# lamp_board_simple.net
KiCad netlist of a schematic drawn in EAGLE
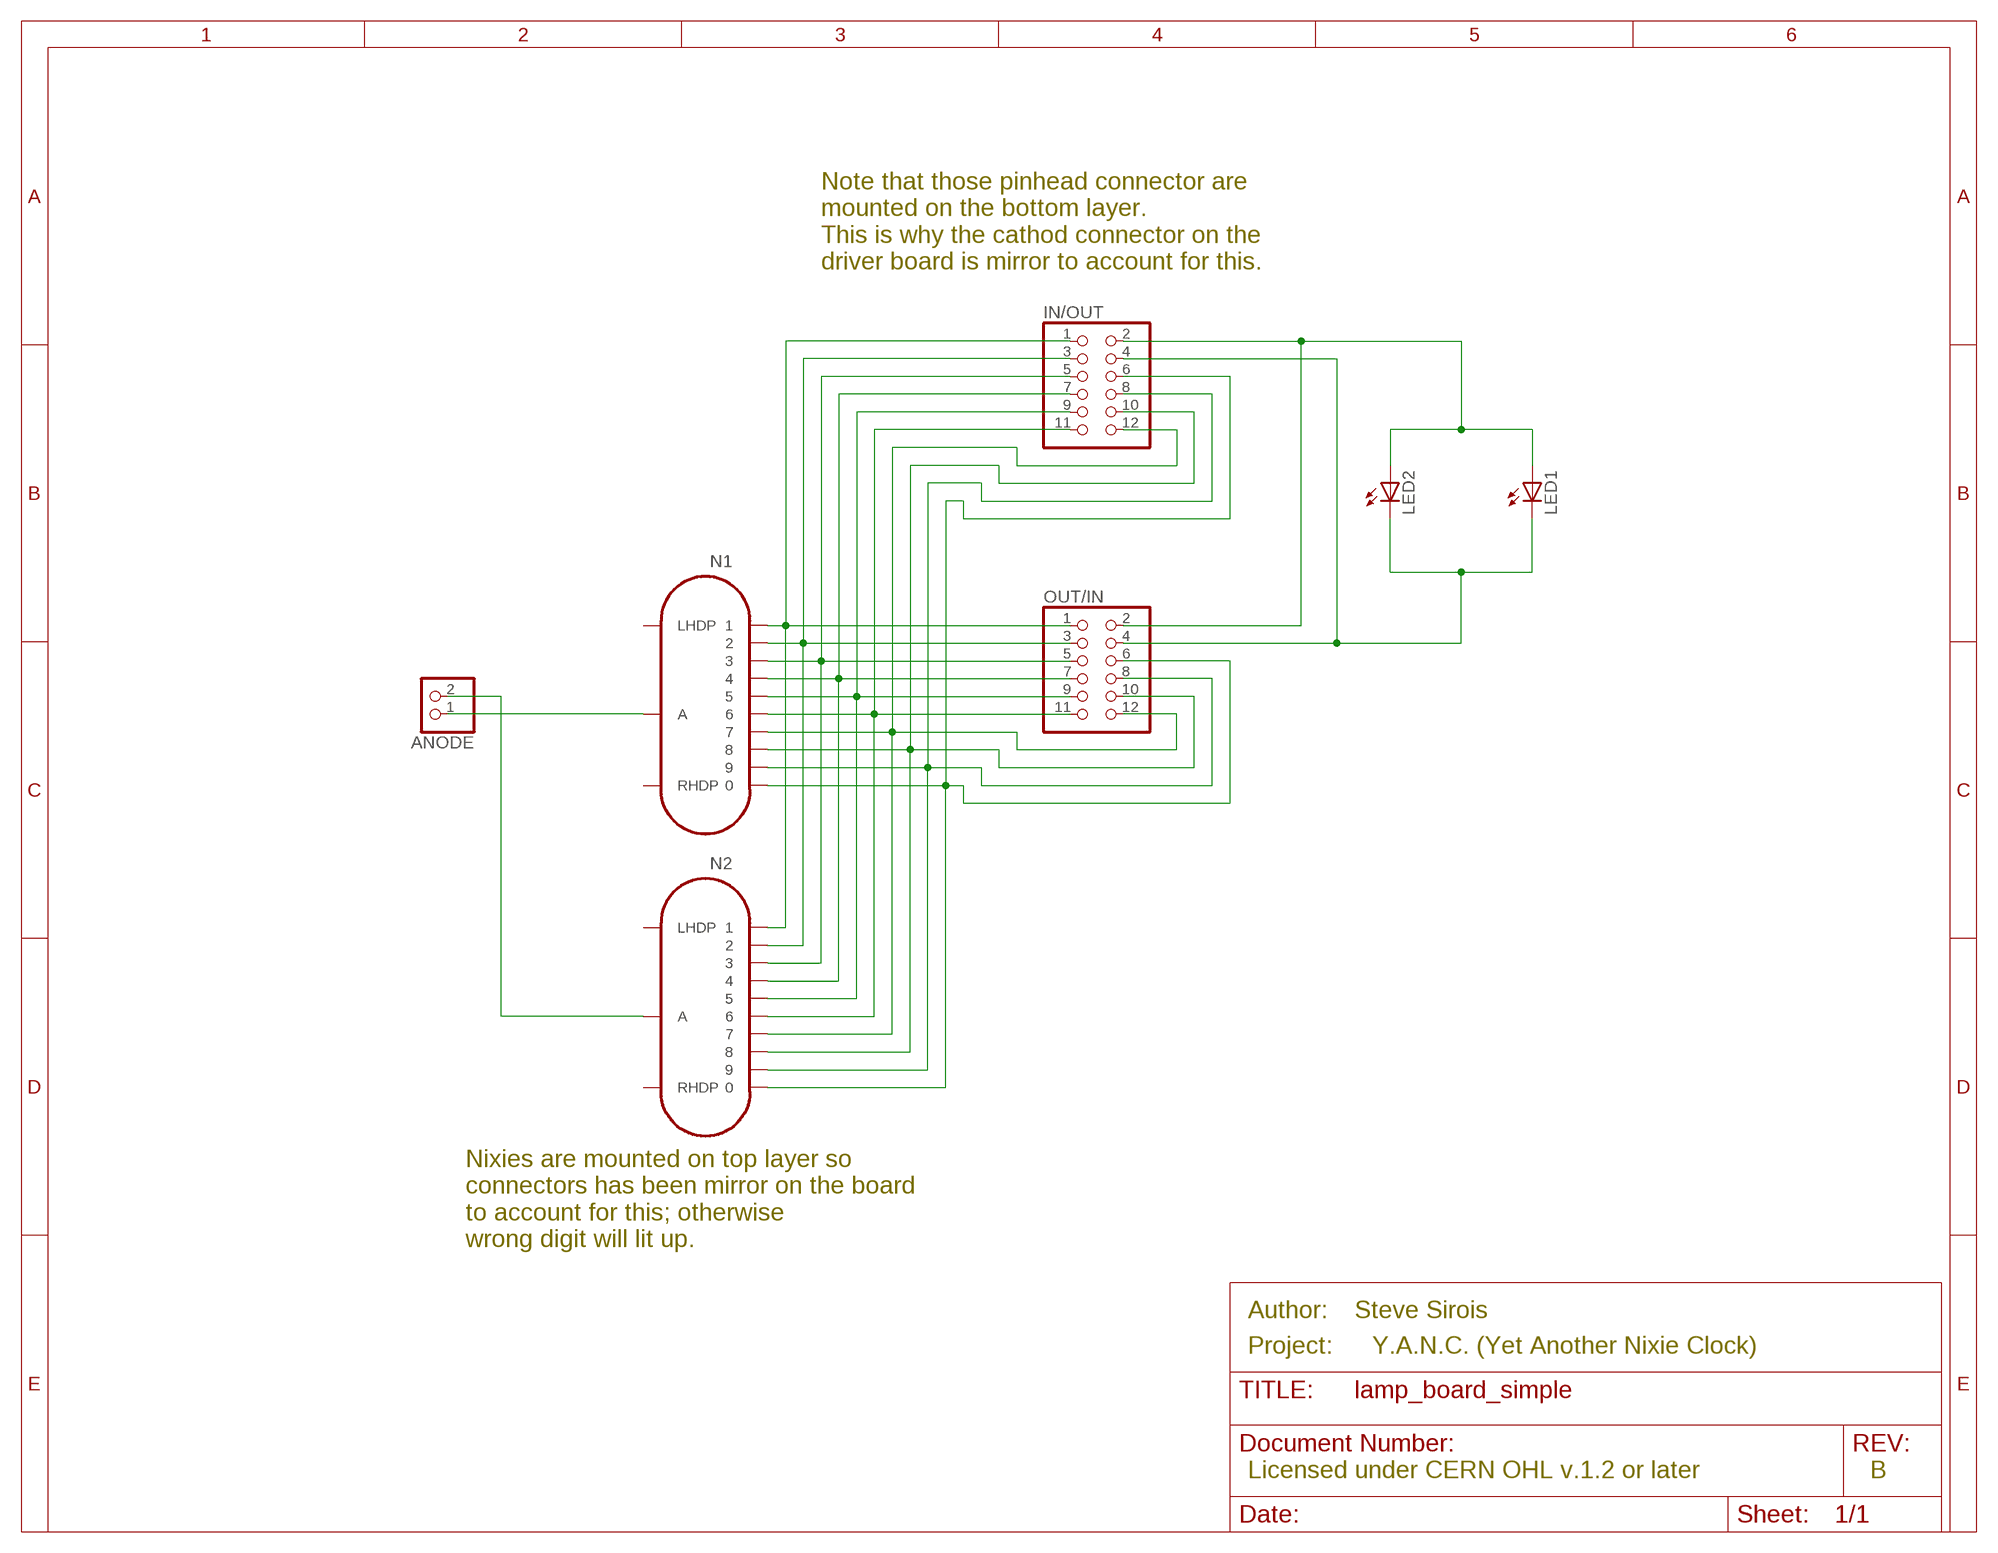
[diagram p0: schematic, sheet 1]

(export (version "E")
  (design (tool "Eeschema 10.0.6"))
  (components
    (comp (ref "ANODE")
      (value "PINHD-1X2/90")
      (footprint "eagle-import:1X02_90")
      (libsource (lib "eagle-import") (part "PINHD-1X2/90"))
    )
    (comp (ref "IN/OUT")
      (value "PINHD-2X6/90")
      (footprint "eagle-import:2X06_90")
      (libsource (lib "eagle-import") (part "PINHD-2X6/90"))
    )
    (comp (ref "LED1")
      (value "LED5MM")
      (footprint "eagle-import:LED5MM")
      (libsource (lib "eagle-import") (part "LED5MM"))
    )
    (comp (ref "LED2")
      (value "LED5MM")
      (footprint "eagle-import:LED5MM")
      (libsource (lib "eagle-import") (part "LED5MM"))
    )
    (comp (ref "N1")
      (value "IN-14")
      (footprint "eagle-import:IN-14")
      (libsource (lib "eagle-import") (part "IN-14"))
    )
    (comp (ref "N2")
      (value "IN-14")
      (footprint "eagle-import:IN-14")
      (libsource (lib "eagle-import") (part "IN-14"))
    )
    (comp (ref "OUT/IN")
      (value "PINHD-2X6/90")
      (footprint "eagle-import:2X06_90")
      (libsource (lib "eagle-import") (part "PINHD-2X6/90"))
    )
  )
  (nets
    (net (code "1") (name "Net-(ANODE-Pad1)") (class "Default")
      (node (ref "ANODE") (pin "1") (pinfunction "1_1") (pintype "passive"))
      (node (ref "N1") (pin "A") (pinfunction "A_A") (pintype "bidirectional"))
    )
    (net (code "2") (name "Net-(ANODE-Pad2)") (class "Default")
      (node (ref "ANODE") (pin "2") (pinfunction "2_2") (pintype "passive"))
      (node (ref "N2") (pin "A") (pinfunction "A_A") (pintype "bidirectional"))
    )
    (net (code "3") (name "Net-(IN/OUT-Pad1)") (class "Default")
      (node (ref "IN/OUT") (pin "1") (pinfunction "1_1") (pintype "passive"))
      (node (ref "N1") (pin "1") (pinfunction "1_1") (pintype "bidirectional"))
      (node (ref "N2") (pin "1") (pinfunction "1_1") (pintype "bidirectional"))
      (node (ref "OUT/IN") (pin "1") (pinfunction "1_1") (pintype "passive"))
    )
    (net (code "4") (name "Net-(IN/OUT-Pad2)") (class "Default")
      (node (ref "IN/OUT") (pin "2") (pinfunction "2_2") (pintype "passive"))
      (node (ref "LED1") (pin "A") (pinfunction "A_A") (pintype "passive"))
      (node (ref "LED2") (pin "A") (pinfunction "A_A") (pintype "passive"))
      (node (ref "OUT/IN") (pin "2") (pinfunction "2_2") (pintype "passive"))
    )
    (net (code "5") (name "Net-(IN/OUT-Pad3)") (class "Default")
      (node (ref "IN/OUT") (pin "3") (pinfunction "3_3") (pintype "passive"))
      (node (ref "N1") (pin "2") (pinfunction "2_2") (pintype "bidirectional"))
      (node (ref "N2") (pin "2") (pinfunction "2_2") (pintype "bidirectional"))
      (node (ref "OUT/IN") (pin "3") (pinfunction "3_3") (pintype "passive"))
    )
    (net (code "6") (name "Net-(IN/OUT-Pad5)") (class "Default")
      (node (ref "IN/OUT") (pin "5") (pinfunction "5_5") (pintype "passive"))
      (node (ref "N1") (pin "3") (pinfunction "3_3") (pintype "bidirectional"))
      (node (ref "N2") (pin "3") (pinfunction "3_3") (pintype "bidirectional"))
      (node (ref "OUT/IN") (pin "5") (pinfunction "5_5") (pintype "passive"))
    )
    (net (code "7") (name "Net-(IN/OUT-Pad6)") (class "Default")
      (node (ref "IN/OUT") (pin "6") (pinfunction "6_6") (pintype "passive"))
      (node (ref "N1") (pin "0") (pinfunction "0_0") (pintype "bidirectional"))
      (node (ref "N2") (pin "0") (pinfunction "0_0") (pintype "bidirectional"))
      (node (ref "OUT/IN") (pin "6") (pinfunction "6_6") (pintype "passive"))
    )
    (net (code "8") (name "Net-(IN/OUT-Pad7)") (class "Default")
      (node (ref "IN/OUT") (pin "7") (pinfunction "7_7") (pintype "passive"))
      (node (ref "N1") (pin "4") (pinfunction "4_4") (pintype "bidirectional"))
      (node (ref "N2") (pin "4") (pinfunction "4_4") (pintype "bidirectional"))
      (node (ref "OUT/IN") (pin "7") (pinfunction "7_7") (pintype "passive"))
    )
    (net (code "9") (name "Net-(IN/OUT-Pad8)") (class "Default")
      (node (ref "IN/OUT") (pin "8") (pinfunction "8_8") (pintype "passive"))
      (node (ref "N1") (pin "9") (pinfunction "9_9") (pintype "bidirectional"))
      (node (ref "N2") (pin "9") (pinfunction "9_9") (pintype "bidirectional"))
      (node (ref "OUT/IN") (pin "8") (pinfunction "8_8") (pintype "passive"))
    )
    (net (code "10") (name "Net-(IN/OUT-Pad9)") (class "Default")
      (node (ref "IN/OUT") (pin "9") (pinfunction "9_9") (pintype "passive"))
      (node (ref "N1") (pin "5") (pinfunction "5_5") (pintype "bidirectional"))
      (node (ref "N2") (pin "5") (pinfunction "5_5") (pintype "bidirectional"))
      (node (ref "OUT/IN") (pin "9") (pinfunction "9_9") (pintype "passive"))
    )
    (net (code "11") (name "Net-(IN/OUT-Pad10)") (class "Default")
      (node (ref "IN/OUT") (pin "10") (pinfunction "10_10") (pintype "passive"))
      (node (ref "N1") (pin "8") (pinfunction "8_8") (pintype "bidirectional"))
      (node (ref "N2") (pin "8") (pinfunction "8_8") (pintype "bidirectional"))
      (node (ref "OUT/IN") (pin "10") (pinfunction "10_10") (pintype "passive"))
    )
    (net (code "12") (name "Net-(IN/OUT-Pad11)") (class "Default")
      (node (ref "IN/OUT") (pin "11") (pinfunction "11_11") (pintype "passive"))
      (node (ref "N1") (pin "6") (pinfunction "6_6") (pintype "bidirectional"))
      (node (ref "N2") (pin "6") (pinfunction "6_6") (pintype "bidirectional"))
      (node (ref "OUT/IN") (pin "11") (pinfunction "11_11") (pintype "passive"))
    )
    (net (code "13") (name "Net-(IN/OUT-Pad12)") (class "Default")
      (node (ref "IN/OUT") (pin "12") (pinfunction "12_12") (pintype "passive"))
      (node (ref "N1") (pin "7") (pinfunction "7_7") (pintype "bidirectional"))
      (node (ref "N2") (pin "7") (pinfunction "7_7") (pintype "bidirectional"))
      (node (ref "OUT/IN") (pin "12") (pinfunction "12_12") (pintype "passive"))
    )
    (net (code "14") (name "Net-(LED1-C)") (class "Default")
      (node (ref "IN/OUT") (pin "4") (pinfunction "4_4") (pintype "passive"))
      (node (ref "LED1") (pin "K") (pinfunction "C_K") (pintype "passive"))
      (node (ref "LED2") (pin "K") (pinfunction "C_K") (pintype "passive"))
      (node (ref "OUT/IN") (pin "4") (pinfunction "4_4") (pintype "passive"))
    )
    (net (code "15") (name "unconnected-(N1-PadLHDP)") (class "Default")
      (node (ref "N1") (pin "LHDP") (pinfunction "LHDP_LHDP") (pintype "bidirectional"))
    )
    (net (code "16") (name "unconnected-(N1-PadRHDP)") (class "Default")
      (node (ref "N1") (pin "RHDP") (pinfunction "RHDP_RHDP") (pintype "bidirectional"))
    )
    (net (code "17") (name "unconnected-(N2-PadLHDP)") (class "Default")
      (node (ref "N2") (pin "LHDP") (pinfunction "LHDP_LHDP") (pintype "bidirectional"))
    )
    (net (code "18") (name "unconnected-(N2-PadRHDP)") (class "Default")
      (node (ref "N2") (pin "RHDP") (pinfunction "RHDP_RHDP") (pintype "bidirectional"))
    )
  )
)
